# 10_CONNECTOR.net
KiCad netlist of a schematic drawn in Altium Designer
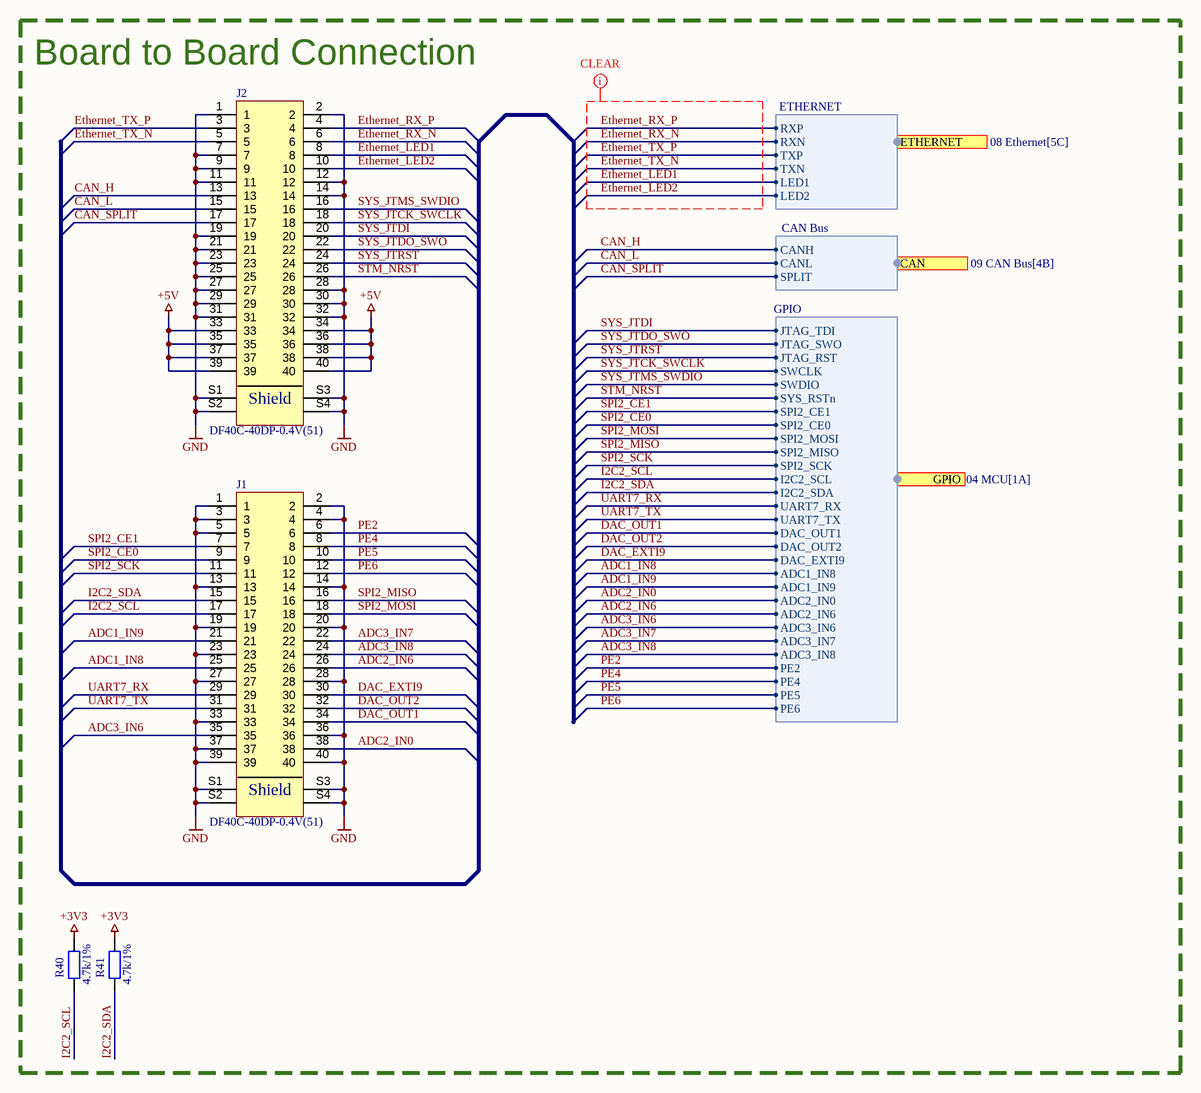
[diagram p0: 10 CONNECTOR.SchDoc]

(export (version "E")
  (design (tool "Eeschema 10.0.6"))
  (components
    (comp (ref "J1")
      (value "DF40C-40DP-0.4V(51)")
      (footprint "DF40C-40DP-0.4V(51)")
      (description "40 Position Connector Plug, Outer Shroud Contacts Surface Mount Gold")
      (libsource (lib "Symbol") (part "DF40C-40DP-0.4V(51)"))
    )
    (comp (ref "J2")
      (value "DF40C-40DP-0.4V(51)")
      (footprint "DF40C-40DP-0.4V(51)")
      (description "40 Position Connector Plug, Outer Shroud Contacts Surface Mount Gold")
      (libsource (lib "Symbol") (part "DF40C-40DP-0.4V(51)"))
    )
    (comp (ref "R40")
      (value "4.7k/1%")
      (footprint "RESC1005X04M-0402")
      (description "4.7 kOhms ±1% 0.063W, 1/16W Chip Resistor 0402 (1005 Metric) Moisture Resistant Thick Film")
      (fields (field (name "MPN") "RC0402FR-074K7L"))
      (libsource (lib "Symbol") (part "RC0402FR-074K7L"))
    )
    (comp (ref "R41")
      (value "4.7k/1%")
      (footprint "RESC1005X04M-0402")
      (description "4.7 kOhms ±1% 0.063W, 1/16W Chip Resistor 0402 (1005 Metric) Moisture Resistant Thick Film")
      (fields (field (name "MPN") "RC0402FR-074K7L"))
      (libsource (lib "Symbol") (part "RC0402FR-074K7L"))
    )
  )
  (nets
    (net (code "5") (name "+3V3") (class "Default")
      (node (ref "R40") (pin "2") (pinfunction "2_2") (pintype "passive"))
      (node (ref "R41") (pin "2") (pinfunction "2_2") (pintype "passive"))
    )
    (net (code "6") (name "+5V") (class "Default")
      (node (ref "J2") (pin "33") (pinfunction "33_33") (pintype "passive"))
      (node (ref "J2") (pin "34") (pinfunction "34_34") (pintype "passive"))
      (node (ref "J2") (pin "35") (pinfunction "35_35") (pintype "passive"))
      (node (ref "J2") (pin "36") (pinfunction "36_36") (pintype "passive"))
      (node (ref "J2") (pin "37") (pinfunction "37_37") (pintype "passive"))
      (node (ref "J2") (pin "38") (pinfunction "38_38") (pintype "passive"))
      (node (ref "J2") (pin "39") (pinfunction "39_39") (pintype "passive"))
      (node (ref "J2") (pin "40") (pinfunction "40_40") (pintype "passive"))
    )
    (net (code "7") (name "/ADC1_IN8") (class "Default")
      (node (ref "J1") (pin "25") (pinfunction "25_25") (pintype "passive"))
    )
    (net (code "8") (name "/ADC1_IN9") (class "Default")
      (node (ref "J1") (pin "21") (pinfunction "21_21") (pintype "passive"))
    )
    (net (code "9") (name "/ADC2_IN0") (class "Default")
      (node (ref "J1") (pin "38") (pinfunction "38_38") (pintype "passive"))
    )
    (net (code "10") (name "/ADC2_IN6") (class "Default")
      (node (ref "J1") (pin "26") (pinfunction "26_26") (pintype "passive"))
    )
    (net (code "11") (name "/ADC3_IN6") (class "Default")
      (node (ref "J1") (pin "35") (pinfunction "35_35") (pintype "passive"))
    )
    (net (code "12") (name "/ADC3_IN7") (class "Default")
      (node (ref "J1") (pin "22") (pinfunction "22_22") (pintype "passive"))
    )
    (net (code "13") (name "/ADC3_IN8") (class "Default")
      (node (ref "J1") (pin "24") (pinfunction "24_24") (pintype "passive"))
    )
    (net (code "14") (name "/CAN_H") (class "Default")
      (node (ref "J2") (pin "13") (pinfunction "13_13") (pintype "passive"))
    )
    (net (code "15") (name "/CAN_L") (class "Default")
      (node (ref "J2") (pin "15") (pinfunction "15_15") (pintype "passive"))
    )
    (net (code "16") (name "/CAN_SPLIT") (class "Default")
      (node (ref "J2") (pin "17") (pinfunction "17_17") (pintype "passive"))
    )
    (net (code "17") (name "/DAC_EXTI9") (class "Default")
      (node (ref "J1") (pin "30") (pinfunction "30_30") (pintype "passive"))
    )
    (net (code "18") (name "/DAC_OUT1") (class "Default")
      (node (ref "J1") (pin "34") (pinfunction "34_34") (pintype "passive"))
    )
    (net (code "19") (name "/DAC_OUT2") (class "Default")
      (node (ref "J1") (pin "32") (pinfunction "32_32") (pintype "passive"))
    )
    (net (code "20") (name "/Ethernet_LED1") (class "Default")
      (node (ref "J2") (pin "8") (pinfunction "8_8") (pintype "passive"))
    )
    (net (code "21") (name "/Ethernet_LED2") (class "Default")
      (node (ref "J2") (pin "10") (pinfunction "10_10") (pintype "passive"))
    )
    (net (code "22") (name "/Ethernet_RX_N") (class "Default")
      (node (ref "J2") (pin "6") (pinfunction "6_6") (pintype "passive"))
    )
    (net (code "23") (name "/Ethernet_RX_P") (class "Default")
      (node (ref "J2") (pin "4") (pinfunction "4_4") (pintype "passive"))
    )
    (net (code "24") (name "/Ethernet_TX_N") (class "Default")
      (node (ref "J2") (pin "5") (pinfunction "5_5") (pintype "passive"))
    )
    (net (code "25") (name "/Ethernet_TX_P") (class "Default")
      (node (ref "J2") (pin "3") (pinfunction "3_3") (pintype "passive"))
    )
    (net (code "26") (name "/I2C2_SCL") (class "Default")
      (node (ref "J1") (pin "17") (pinfunction "17_17") (pintype "passive"))
      (node (ref "R40") (pin "1") (pinfunction "1_1") (pintype "passive"))
    )
    (net (code "27") (name "/I2C2_SDA") (class "Default")
      (node (ref "J1") (pin "15") (pinfunction "15_15") (pintype "passive"))
      (node (ref "R41") (pin "1") (pinfunction "1_1") (pintype "passive"))
    )
    (net (code "28") (name "/PE2") (class "Default")
      (node (ref "J1") (pin "6") (pinfunction "6_6") (pintype "passive"))
    )
    (net (code "29") (name "/PE4") (class "Default")
      (node (ref "J1") (pin "8") (pinfunction "8_8") (pintype "passive"))
    )
    (net (code "30") (name "/PE5") (class "Default")
      (node (ref "J1") (pin "10") (pinfunction "10_10") (pintype "passive"))
    )
    (net (code "31") (name "/PE6") (class "Default")
      (node (ref "J1") (pin "12") (pinfunction "12_12") (pintype "passive"))
    )
    (net (code "32") (name "/SPI2_CE0") (class "Default")
      (node (ref "J1") (pin "9") (pinfunction "9_9") (pintype "passive"))
    )
    (net (code "33") (name "/SPI2_CE1") (class "Default")
      (node (ref "J1") (pin "7") (pinfunction "7_7") (pintype "passive"))
    )
    (net (code "34") (name "/SPI2_MISO") (class "Default")
      (node (ref "J1") (pin "16") (pinfunction "16_16") (pintype "passive"))
    )
    (net (code "35") (name "/SPI2_MOSI") (class "Default")
      (node (ref "J1") (pin "18") (pinfunction "18_18") (pintype "passive"))
    )
    (net (code "36") (name "/SPI2_SCK") (class "Default")
      (node (ref "J1") (pin "11") (pinfunction "11_11") (pintype "passive"))
    )
    (net (code "37") (name "/STM_NRST") (class "Default")
      (node (ref "J2") (pin "26") (pinfunction "26_26") (pintype "passive"))
    )
    (net (code "38") (name "/SYS_JTCK_SWCLK") (class "Default")
      (node (ref "J2") (pin "18") (pinfunction "18_18") (pintype "passive"))
    )
    (net (code "39") (name "/SYS_JTDI") (class "Default")
      (node (ref "J2") (pin "20") (pinfunction "20_20") (pintype "passive"))
    )
    (net (code "40") (name "/SYS_JTDO_SWO") (class "Default")
      (node (ref "J2") (pin "22") (pinfunction "22_22") (pintype "passive"))
    )
    (net (code "41") (name "/SYS_JTMS_SWDIO") (class "Default")
      (node (ref "J2") (pin "16") (pinfunction "16_16") (pintype "passive"))
    )
    (net (code "42") (name "/SYS_JTRST") (class "Default")
      (node (ref "J2") (pin "24") (pinfunction "24_24") (pintype "passive"))
    )
    (net (code "43") (name "/UART7_RX") (class "Default")
      (node (ref "J1") (pin "29") (pinfunction "29_29") (pintype "passive"))
    )
    (net (code "44") (name "/UART7_TX") (class "Default")
      (node (ref "J1") (pin "31") (pinfunction "31_31") (pintype "passive"))
    )
    (net (code "48") (name "GND") (class "Default")
      (node (ref "J1") (pin "1") (pinfunction "1_1") (pintype "passive"))
      (node (ref "J1") (pin "13") (pinfunction "13_13") (pintype "passive"))
      (node (ref "J1") (pin "14") (pinfunction "14_14") (pintype "passive"))
      (node (ref "J1") (pin "19") (pinfunction "19_19") (pintype "passive"))
      (node (ref "J1") (pin "2") (pinfunction "2_2") (pintype "passive"))
      (node (ref "J1") (pin "20") (pinfunction "20_20") (pintype "passive"))
      (node (ref "J1") (pin "23") (pinfunction "23_23") (pintype "passive"))
      (node (ref "J1") (pin "27") (pinfunction "27_27") (pintype "passive"))
      (node (ref "J1") (pin "28") (pinfunction "28_28") (pintype "passive"))
      (node (ref "J1") (pin "3") (pinfunction "3_3") (pintype "passive"))
      (node (ref "J1") (pin "33") (pinfunction "33_33") (pintype "passive"))
      (node (ref "J1") (pin "36") (pinfunction "36_36") (pintype "passive"))
      (node (ref "J1") (pin "37") (pinfunction "37_37") (pintype "passive"))
      (node (ref "J1") (pin "39") (pinfunction "39_39") (pintype "passive"))
      (node (ref "J1") (pin "4") (pinfunction "4_4") (pintype "passive"))
      (node (ref "J1") (pin "40") (pinfunction "40_40") (pintype "passive"))
      (node (ref "J1") (pin "5") (pinfunction "5_5") (pintype "passive"))
      (node (ref "J1") (pin "S1") (pintype "passive"))
      (node (ref "J1") (pin "S2") (pintype "passive"))
      (node (ref "J1") (pin "S3") (pintype "passive"))
      (node (ref "J1") (pin "S4") (pintype "passive"))
      (node (ref "J2") (pin "1") (pinfunction "1_1") (pintype "passive"))
      (node (ref "J2") (pin "11") (pinfunction "11_11") (pintype "passive"))
      (node (ref "J2") (pin "12") (pinfunction "12_12") (pintype "passive"))
      (node (ref "J2") (pin "14") (pinfunction "14_14") (pintype "passive"))
      (node (ref "J2") (pin "19") (pinfunction "19_19") (pintype "passive"))
      (node (ref "J2") (pin "2") (pinfunction "2_2") (pintype "passive"))
      (node (ref "J2") (pin "21") (pinfunction "21_21") (pintype "passive"))
      (node (ref "J2") (pin "23") (pinfunction "23_23") (pintype "passive"))
      (node (ref "J2") (pin "25") (pinfunction "25_25") (pintype "passive"))
      (node (ref "J2") (pin "27") (pinfunction "27_27") (pintype "passive"))
      (node (ref "J2") (pin "28") (pinfunction "28_28") (pintype "passive"))
      (node (ref "J2") (pin "29") (pinfunction "29_29") (pintype "passive"))
      (node (ref "J2") (pin "30") (pinfunction "30_30") (pintype "passive"))
      (node (ref "J2") (pin "31") (pinfunction "31_31") (pintype "passive"))
      (node (ref "J2") (pin "32") (pinfunction "32_32") (pintype "passive"))
      (node (ref "J2") (pin "7") (pinfunction "7_7") (pintype "passive"))
      (node (ref "J2") (pin "9") (pinfunction "9_9") (pintype "passive"))
      (node (ref "J2") (pin "S1") (pintype "passive"))
      (node (ref "J2") (pin "S2") (pintype "passive"))
      (node (ref "J2") (pin "S3") (pintype "passive"))
      (node (ref "J2") (pin "S4") (pintype "passive"))
    )
  )
)
